# NRC7394-TX.net
KiCad netlist of a schematic drawn in Altium Designer
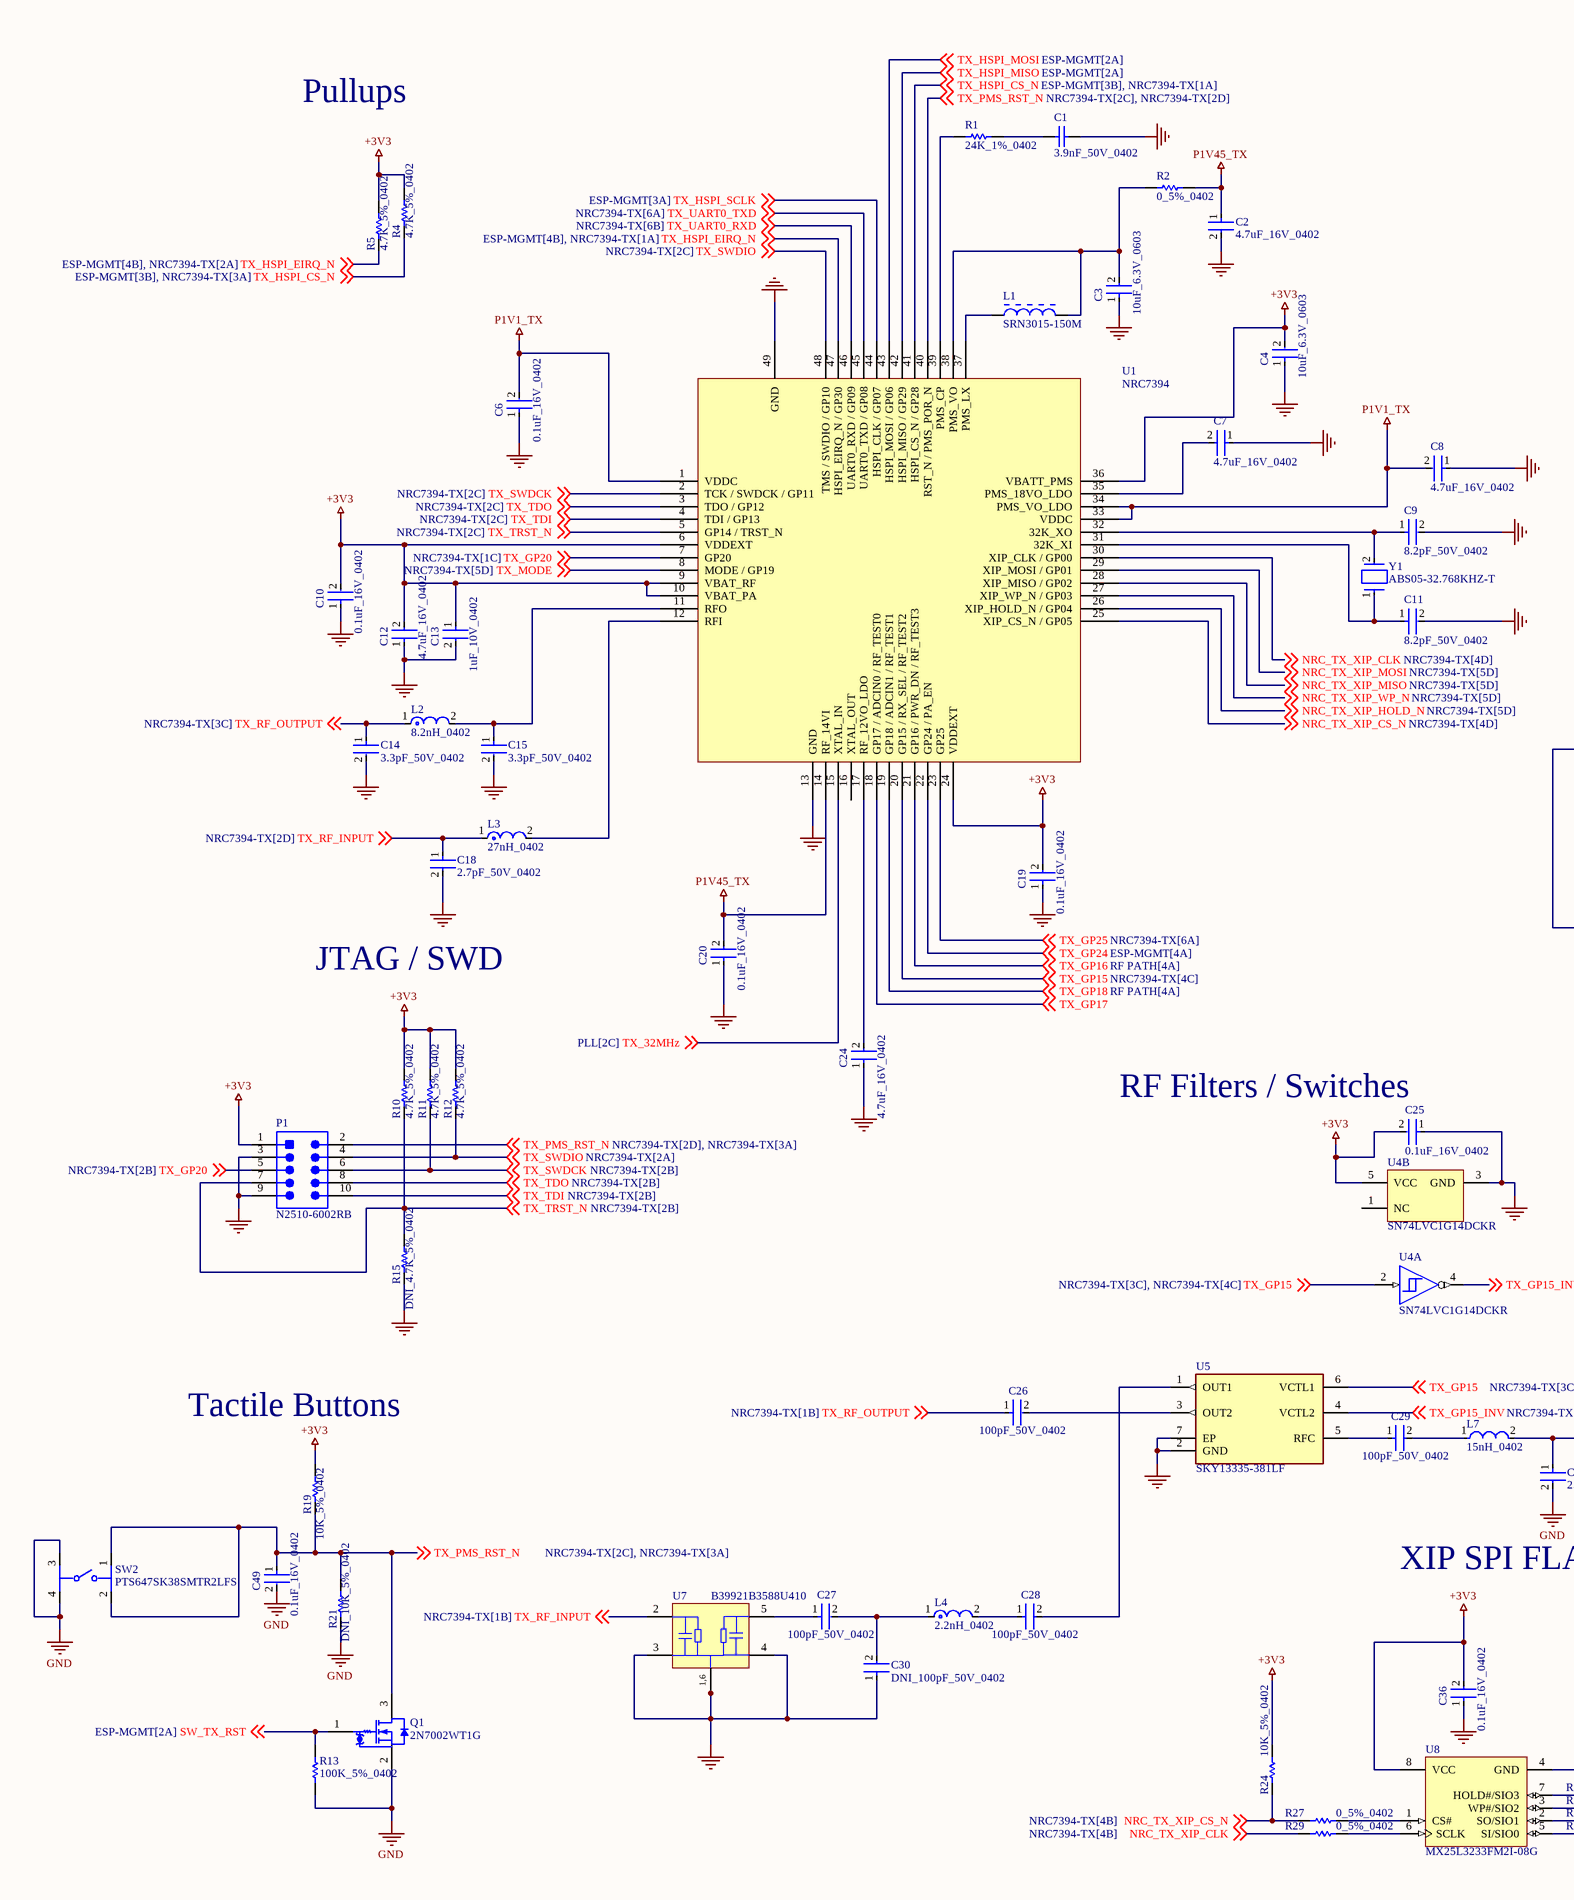
[diagram p0: NRC7394-TX.SchDoc, left]
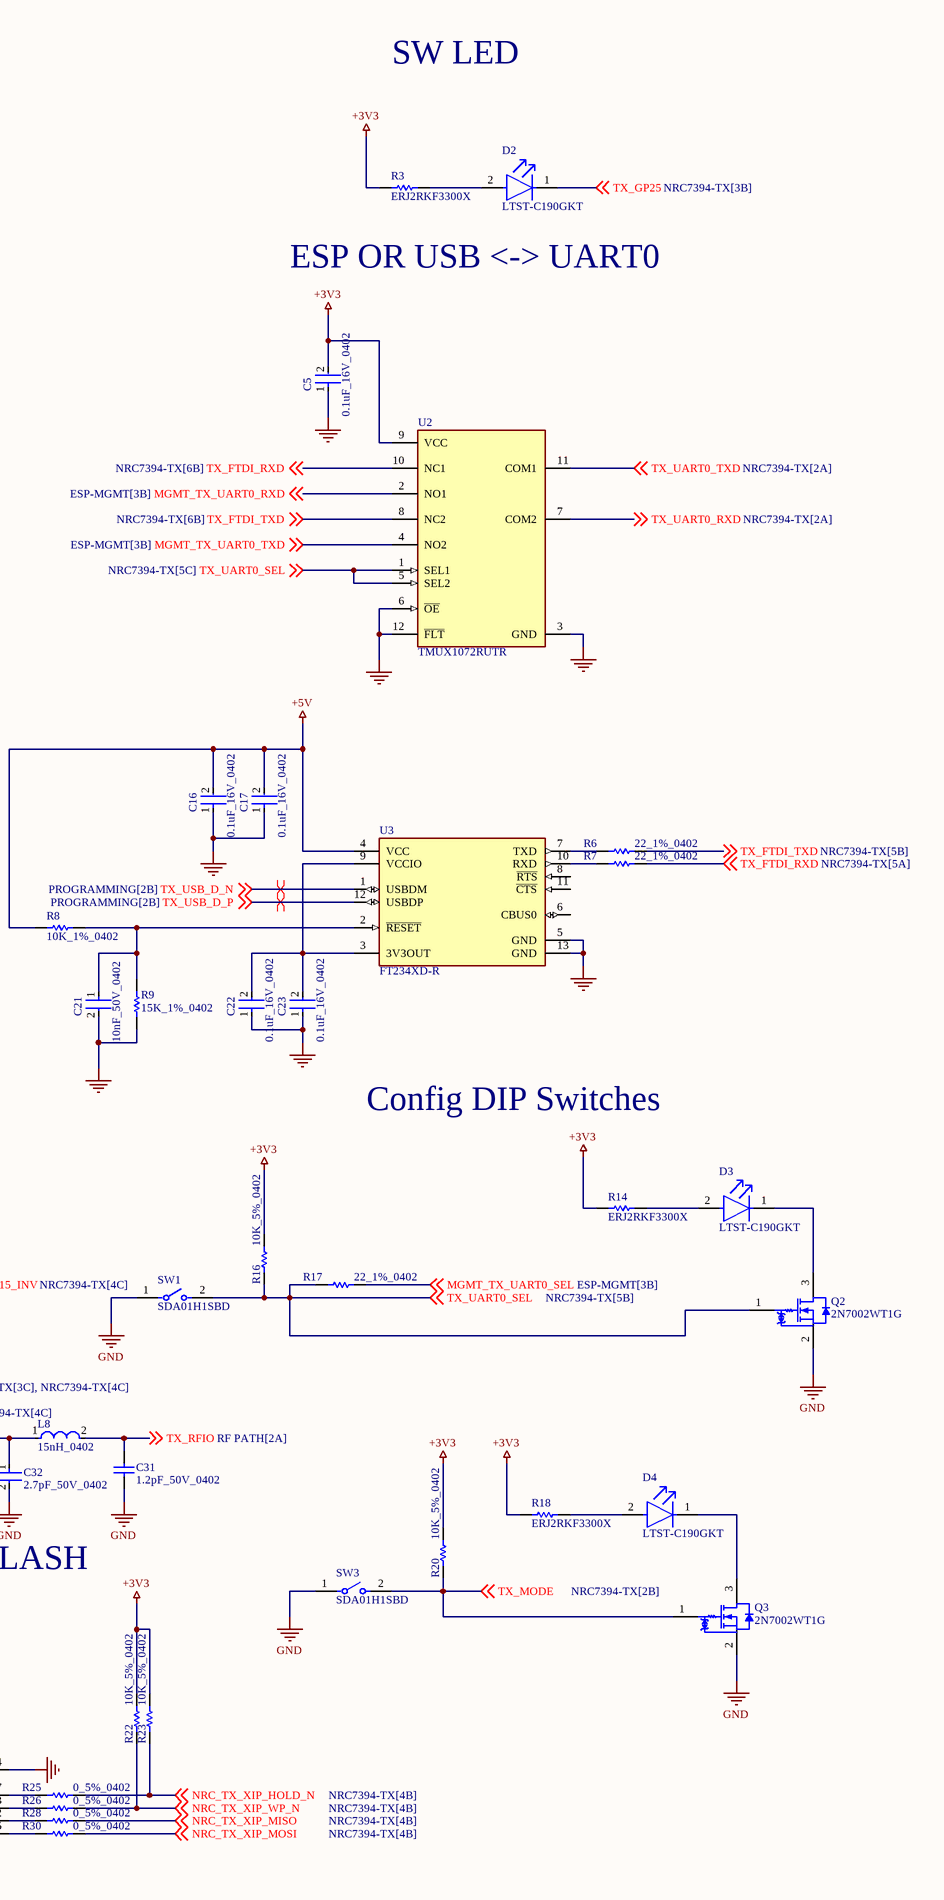
[diagram p1: NRC7394-TX.SchDoc, right]

(export (version "E")
  (design (tool "Eeschema 10.0.6"))
  (components
    (comp (ref "C1")
      (value "3.9nF_50V_0402")
      (footprint "CAPC1005X56X25LL10T15")
      (fields
        (field (name "MANUFACTURER") "AVX Interconnect / Elco")
        (field (name "PART NUMBER") "04025C392JAT2A")
      )
      (libsource (lib "Altium Content Vault") (part "CAP"))
    )
    (comp (ref "C2")
      (value "4.7uF_16V_0402")
      (footprint "FP-CL829-IPC_C")
      (description "Cap Ceramic 4.7uF 16V X5R ±20% SMD 0402 +85°C Paper T/R")
      (fields (field (name "TOLERANCE") "20%"))
      (libsource (lib "Altium Content Vault") (part "b4654b650e69147ec39a6b967a45e02"))
    )
    (comp (ref "C3")
      (value "10uF_6.3V_0603")
      (footprint "FP-GRM188-0_1-e0_2_0_55-IPC_A")
      (description "Chip Multilayer Ceramic Capacitors for General Purpose, 0603, 10uF, X5R, 15%, 20%, 6.3V")
      (fields (field (name "VOLTAGE") "6.3V") (field (name "TOLERANCE") "20%"))
      (libsource (lib "Altium Content Vault") (part "02cd4be3c70576c341d710602a673aa"))
    )
    (comp (ref "C4")
      (value "10uF_6.3V_0603")
      (footprint "FP-GRM188-0_1-e0_2_0_55-IPC_A")
      (description "Chip Multilayer Ceramic Capacitors for General Purpose, 0603, 10uF, X5R, 15%, 20%, 6.3V")
      (fields (field (name "VOLTAGE") "6.3V") (field (name "TOLERANCE") "20%"))
      (libsource (lib "Altium Content Vault") (part "02cd4be3c70576c341d710602a673aa"))
    )
    (comp (ref "C5")
      (value "0.1uF_16V_0402")
      (footprint "FP-C0402-BB-MFG")
      (description "CAP CER 0.1UF 16V 20% X7R 0402")
      (fields
        (field (name "MANUFACTURER") "Kemet")
        (field (name "OCTOPART") "https://octopart.com/c0402c104m4ractu-kemet-10476575")
      )
      (libsource (lib "Altium Content Vault") (part "b4654b650e69147ec39a6b967a45e02"))
    )
    (comp (ref "C6")
      (value "0.1uF_16V_0402")
      (footprint "FP-C0402-BB-MFG")
      (description "CAP CER 0.1UF 16V 20% X7R 0402")
      (fields
        (field (name "MANUFACTURER") "Kemet")
        (field (name "OCTOPART") "https://octopart.com/c0402c104m4ractu-kemet-10476575")
      )
      (libsource (lib "Altium Content Vault") (part "b4654b650e69147ec39a6b967a45e02"))
    )
    (comp (ref "C7")
      (value "4.7uF_16V_0402")
      (footprint "FP-CL829-IPC_C")
      (description "Cap Ceramic 4.7uF 16V X5R ±20% SMD 0402 +85°C Paper T/R")
      (fields (field (name "TOLERANCE") "20%"))
      (libsource (lib "Altium Content Vault") (part "b4654b650e69147ec39a6b967a45e02"))
    )
    (comp (ref "C8")
      (value "4.7uF_16V_0402")
      (footprint "FP-CL829-IPC_C")
      (description "Cap Ceramic 4.7uF 16V X5R ±20% SMD 0402 +85°C Paper T/R")
      (fields (field (name "TOLERANCE") "20%"))
      (libsource (lib "Altium Content Vault") (part "b4654b650e69147ec39a6b967a45e02"))
    )
    (comp (ref "C9")
      (value "8.2pF_50V_0402")
      (footprint "FP-C0402-BB-MFG")
      (description "CAP CER 8.2PF 50V NP0 0402")
      (fields
        (field (name "MANUFACTURER PART NUMBER") "C0402C829C5GACTU")
        (field (name "TOLERANCE") "0.25 pF")
      )
      (libsource (lib "Altium Content Vault") (part "b4654b650e69147ec39a6b967a45e02"))
    )
    (comp (ref "C10")
      (value "0.1uF_16V_0402")
      (footprint "FP-C0402-BB-MFG")
      (description "CAP CER 0.1UF 16V 20% X7R 0402")
      (fields
        (field (name "MANUFACTURER") "Kemet")
        (field (name "OCTOPART") "https://octopart.com/c0402c104m4ractu-kemet-10476575")
      )
      (libsource (lib "Altium Content Vault") (part "b4654b650e69147ec39a6b967a45e02"))
    )
    (comp (ref "C11")
      (value "8.2pF_50V_0402")
      (footprint "FP-C0402-BB-MFG")
      (description "CAP CER 8.2PF 50V NP0 0402")
      (fields
        (field (name "MANUFACTURER PART NUMBER") "C0402C829C5GACTU")
        (field (name "TOLERANCE") "0.25 pF")
      )
      (libsource (lib "Altium Content Vault") (part "b4654b650e69147ec39a6b967a45e02"))
    )
    (comp (ref "C12")
      (value "4.7uF_16V_0402")
      (footprint "FP-CL829-IPC_C")
      (description "Cap Ceramic 4.7uF 16V X5R ±20% SMD 0402 +85°C Paper T/R")
      (fields (field (name "TOLERANCE") "20%"))
      (libsource (lib "Altium Content Vault") (part "b4654b650e69147ec39a6b967a45e02"))
    )
    (comp (ref "C13")
      (value "1uF_10V_0402")
      (footprint "FP-C0402C105K8PACTU-MFG")
      (description "CAP CER 1UF 10V X5R 0402")
      (fields (field (name "VOLTAGE") "10V") (field (name "TOLERANCE") "10%"))
      (libsource (lib "Altium Content Vault") (part "11868f565c42a9108669ba33697ecf6"))
    )
    (comp (ref "C14")
      (value "3.3pF_50V_0402")
      (footprint "FP-C0402-BB-MFG")
      (description "Capacitor: ceramic; MLCC; 3.3pF; 50VDC; C0G; ±0.25pF; SMD; 0402")
      (fields
        (field (name "MANUFACTURER PART NUMBER") "C0402C339C5GACTU")
        (field (name "TOLERANCE") "0.25 pF")
      )
      (libsource (lib "Altium Content Vault") (part "b4654b650e69147ec39a6b967a45e02"))
    )
    (comp (ref "C15")
      (value "3.3pF_50V_0402")
      (footprint "FP-C0402-BB-MFG")
      (description "Capacitor: ceramic; MLCC; 3.3pF; 50VDC; C0G; ±0.25pF; SMD; 0402")
      (fields
        (field (name "MANUFACTURER PART NUMBER") "C0402C339C5GACTU")
        (field (name "TOLERANCE") "0.25 pF")
      )
      (libsource (lib "Altium Content Vault") (part "b4654b650e69147ec39a6b967a45e02"))
    )
    (comp (ref "C16")
      (value "0.1uF_16V_0402")
      (footprint "FP-C0402-BB-MFG")
      (description "CAP CER 0.1UF 16V 20% X7R 0402")
      (fields
        (field (name "MANUFACTURER") "Kemet")
        (field (name "OCTOPART") "https://octopart.com/c0402c104m4ractu-kemet-10476575")
      )
      (libsource (lib "Altium Content Vault") (part "b4654b650e69147ec39a6b967a45e02"))
    )
    (comp (ref "C17")
      (value "0.1uF_16V_0402")
      (footprint "FP-C0402-BB-MFG")
      (description "CAP CER 0.1UF 16V 20% X7R 0402")
      (fields
        (field (name "MANUFACTURER") "Kemet")
        (field (name "OCTOPART") "https://octopart.com/c0402c104m4ractu-kemet-10476575")
      )
      (libsource (lib "Altium Content Vault") (part "b4654b650e69147ec39a6b967a45e02"))
    )
    (comp (ref "C18")
      (value "2.7pF_50V_0402")
      (footprint "FP-GJM155-0_05-IPC_A")
      (description "Multi-Layer Ceramic Capacitor 2.7pF C0G  ±0.1pF 0402 Paper T/R")
      (fields (field (name "VOLTAGE") "50V"))
      (libsource (lib "Altium Content Vault") (part "02cd4be3c70576c341d710602a673aa"))
    )
    (comp (ref "C19")
      (value "0.1uF_16V_0402")
      (footprint "FP-C0402-BB-MFG")
      (description "CAP CER 0.1UF 16V 20% X7R 0402")
      (fields
        (field (name "MANUFACTURER") "Kemet")
        (field (name "OCTOPART") "https://octopart.com/c0402c104m4ractu-kemet-10476575")
      )
      (libsource (lib "Altium Content Vault") (part "b4654b650e69147ec39a6b967a45e02"))
    )
    (comp (ref "C20")
      (value "0.1uF_16V_0402")
      (footprint "FP-C0402-BB-MFG")
      (description "CAP CER 0.1UF 16V 20% X7R 0402")
      (fields
        (field (name "MANUFACTURER") "Kemet")
        (field (name "OCTOPART") "https://octopart.com/c0402c104m4ractu-kemet-10476575")
      )
      (libsource (lib "Altium Content Vault") (part "b4654b650e69147ec39a6b967a45e02"))
    )
    (comp (ref "C21")
      (value "10nF_50V_0402")
      (footprint "FP-CL165-IPC_C")
      (description "Cap Ceramic 10nF 50V X7R ±10% SMD 0402 +125°C Paper T/R")
      (fields (field (name "VOLTAGE") "50V") (field (name "TOLERANCE") "10%"))
      (libsource (lib "Altium Content Vault") (part "b4654b650e69147ec39a6b967a45e02"))
    )
    (comp (ref "C22")
      (value "0.1uF_16V_0402")
      (footprint "FP-C0402-BB-MFG")
      (description "CAP CER 0.1UF 16V 20% X7R 0402")
      (fields
        (field (name "MANUFACTURER") "Kemet")
        (field (name "OCTOPART") "https://octopart.com/c0402c104m4ractu-kemet-10476575")
      )
      (libsource (lib "Altium Content Vault") (part "b4654b650e69147ec39a6b967a45e02"))
    )
    (comp (ref "C23")
      (value "0.1uF_16V_0402")
      (footprint "FP-C0402-BB-MFG")
      (description "CAP CER 0.1UF 16V 20% X7R 0402")
      (fields
        (field (name "MANUFACTURER") "Kemet")
        (field (name "OCTOPART") "https://octopart.com/c0402c104m4ractu-kemet-10476575")
      )
      (libsource (lib "Altium Content Vault") (part "b4654b650e69147ec39a6b967a45e02"))
    )
    (comp (ref "C24")
      (value "4.7uF_16V_0402")
      (footprint "FP-CL829-IPC_C")
      (description "Cap Ceramic 4.7uF 16V X5R ±20% SMD 0402 +85°C Paper T/R")
      (fields (field (name "TOLERANCE") "20%"))
      (libsource (lib "Altium Content Vault") (part "b4654b650e69147ec39a6b967a45e02"))
    )
    (comp (ref "C25")
      (value "0.1uF_16V_0402")
      (footprint "FP-C0402-BB-MFG")
      (description "CAP CER 0.1UF 16V 20% X7R 0402")
      (fields
        (field (name "MANUFACTURER") "Kemet")
        (field (name "OCTOPART") "https://octopart.com/c0402c104m4ractu-kemet-10476575")
      )
      (libsource (lib "Altium Content Vault") (part "b4654b650e69147ec39a6b967a45e02"))
    )
    (comp (ref "C26")
      (value "100pF_50V_0402")
      (footprint "FP-C0402-BB-MFG")
      (description "CAP CER 100PF 50V C0G/NP0 0402")
      (fields (field (name "MANUFACTURER") "Kemet") (field (name "TOLERANCE") "0.05"))
      (libsource (lib "Altium Content Vault") (part "b4654b650e69147ec39a6b967a45e02"))
    )
    (comp (ref "C27")
      (value "100pF_50V_0402")
      (footprint "FP-C0402-BB-MFG")
      (description "CAP CER 100PF 50V C0G/NP0 0402")
      (fields (field (name "MANUFACTURER") "Kemet") (field (name "TOLERANCE") "0.05"))
      (libsource (lib "Altium Content Vault") (part "b4654b650e69147ec39a6b967a45e02"))
    )
    (comp (ref "C28")
      (value "100pF_50V_0402")
      (footprint "FP-C0402-BB-MFG")
      (description "CAP CER 100PF 50V C0G/NP0 0402")
      (fields (field (name "MANUFACTURER") "Kemet") (field (name "TOLERANCE") "0.05"))
      (libsource (lib "Altium Content Vault") (part "b4654b650e69147ec39a6b967a45e02"))
    )
    (comp (ref "C29")
      (value "100pF_50V_0402")
      (footprint "FP-C0402-BB-MFG")
      (description "CAP CER 100PF 50V C0G/NP0 0402")
      (fields (field (name "MANUFACTURER") "Kemet") (field (name "TOLERANCE") "0.05"))
      (libsource (lib "Altium Content Vault") (part "b4654b650e69147ec39a6b967a45e02"))
    )
    (comp (ref "C30")
      (value "DNI_100pF_50V_0402")
      (footprint "FP-C0402-BB-MFG")
      (description "CAP CER 100PF 50V C0G/NP0 0402")
      (fields (field (name "MANUFACTURER") "Kemet") (field (name "TOLERANCE") "0.05"))
      (libsource (lib "Altium Content Vault") (part "b4654b650e69147ec39a6b967a45e02"))
    )
    (comp (ref "C31")
      (value "1.2pF_50V_0402")
      (footprint "CAPC1006X50X20LL10T10")
      (fields
        (field (name "MANUFACTURER") "AVX Interconnect / Elco")
        (field (name "PART NUMBER") "04023J1R2BBSTR")
      )
      (libsource (lib "Altium Content Vault") (part "CAP"))
    )
    (comp (ref "C32")
      (value "2.7pF_50V_0402")
      (footprint "FP-GJM155-0_05-IPC_A")
      (description "Multi-Layer Ceramic Capacitor 2.7pF C0G  ±0.1pF 0402 Paper T/R")
      (fields (field (name "VOLTAGE") "50V"))
      (libsource (lib "Altium Content Vault") (part "02cd4be3c70576c341d710602a673aa"))
    )
    (comp (ref "C36")
      (value "0.1uF_16V_0402")
      (footprint "FP-C0402-BB-MFG")
      (description "CAP CER 0.1UF 16V 20% X7R 0402")
      (fields
        (field (name "MANUFACTURER") "Kemet")
        (field (name "OCTOPART") "https://octopart.com/c0402c104m4ractu-kemet-10476575")
      )
      (libsource (lib "Altium Content Vault") (part "b4654b650e69147ec39a6b967a45e02"))
    )
    (comp (ref "C49")
      (value "0.1uF_16V_0402")
      (footprint "FP-C0402-BB-MFG")
      (description "CAP CER 0.1UF 16V 20% X7R 0402")
      (fields
        (field (name "MANUFACTURER") "Kemet")
        (field (name "OCTOPART") "https://octopart.com/c0402c104m4ractu-kemet-10476575")
      )
      (libsource (lib "Altium Content Vault") (part "b4654b650e69147ec39a6b967a45e02"))
    )
    (comp (ref "D2")
      (value "LTST-C190GKT")
      (footprint "FP-LTST-C190GKT-MFG")
      (description "LED GREEN CLEAR CHIP SMD")
      (fields (field (name "VOLTAGE") "2V"))
      (libsource (lib "Altium Content Vault") (part "8706943c75ba83719d021d2fdc84c58"))
    )
    (comp (ref "D3")
      (value "LTST-C190GKT")
      (footprint "FP-LTST-C190GKT-MFG")
      (description "LED GREEN CLEAR CHIP SMD")
      (fields (field (name "VOLTAGE") "2V"))
      (libsource (lib "Altium Content Vault") (part "8706943c75ba83719d021d2fdc84c58"))
    )
    (comp (ref "D4")
      (value "LTST-C190GKT")
      (footprint "FP-LTST-C190GKT-MFG")
      (description "LED GREEN CLEAR CHIP SMD")
      (fields (field (name "VOLTAGE") "2V"))
      (libsource (lib "Altium Content Vault") (part "8706943c75ba83719d021d2fdc84c58"))
    )
    (comp (ref "L1")
      (value "SRN3015-150M")
      (footprint "BOUR-SRN3015-2_V")
      (fields (field (name "MANUFACTURER") "Bourns"))
      (libsource (lib "Altium Content Vault") (part "BOUR-IND-2A"))
    )
    (comp (ref "L2")
      (value "8.2nH_0402")
      (footprint "FP-LQG15HH_02-IPC_B")
      (description "Multilayer type RF Inductor 8.2nH ±5% 0.24Ω 550mA 0402")
      (fields (field (name "TOLERANCE") "5%"))
      (libsource (lib "Altium Content Vault") (part "4cc4b267dca4c8e51f7102f422741d8"))
    )
    (comp (ref "L3")
      (value "27nH_0402")
      (footprint "FP-LQG15HH_02-IPC_C")
      (description "Multilayer type RF Inductor 27nH ±5% 0.46Ω 350mA 0402")
      (fields (field (name "TOLERANCE") "5%"))
      (libsource (lib "Altium Content Vault") (part "4cc4b267dca4c8e51f7102f422741d8"))
    )
    (comp (ref "L4")
      (value "2.2nH_0402")
      (footprint "FP-LQG15HH_02-IPC_C")
      (description "Multilayer type RF Inductor 2.2nH ±0.3nH 0.09Ω 900mA 0402")
      (libsource (lib "Altium Content Vault") (part "4cc4b267dca4c8e51f7102f422741d8"))
    )
    (comp (ref "L7")
      (value "15nH_0402")
      (footprint "FP-HK1005-MFG")
      (description "FIXED IND 15NH 320MA 460 MOHM")
      (fields (field (name "TOLERANCE") "5%"))
      (libsource (lib "Altium Content Vault") (part "725321dda6339637d4d059423bc1c3c"))
    )
    (comp (ref "L8")
      (value "15nH_0402")
      (footprint "FP-HK1005-MFG")
      (description "FIXED IND 15NH 320MA 460 MOHM")
      (fields (field (name "TOLERANCE") "5%"))
      (libsource (lib "Altium Content Vault") (part "725321dda6339637d4d059423bc1c3c"))
    )
    (comp (ref "P1")
      (value "N2510-6002RB")
      (footprint "3M-N2510-6002-10_V")
      (fields (field (name "PARTNUMBER") "N2510") (field (name "MANUFACTURER") "3M"))
      (libsource (lib "Altium Content Vault") (part "CN-2P-M-R10"))
    )
    (comp (ref "Q1")
      (value "2N7002WT1G")
      (footprint "ONSC-SC-70-3-419-04_V")
      (description "Small Signal MOSFET, 60 V, 340 mA, Single, N-Channel, 3-Pin SC70, Pb-Free, Tape and Reel")
      (fields (field (name "MANUFACTURER") "On Semiconductor"))
      (libsource (lib "Altium Content Vault") (part "ONSC-NMOS-G1S2D3-3_C"))
    )
    (comp (ref "Q2")
      (value "2N7002WT1G")
      (footprint "ONSC-SC-70-3-419-04_V")
      (description "Small Signal MOSFET, 60 V, 340 mA, Single, N-Channel, 3-Pin SC70, Pb-Free, Tape and Reel")
      (fields (field (name "MANUFACTURER") "On Semiconductor"))
      (libsource (lib "Altium Content Vault") (part "ONSC-NMOS-G1S2D3-3_C"))
    )
    (comp (ref "Q3")
      (value "2N7002WT1G")
      (footprint "ONSC-SC-70-3-419-04_V")
      (description "Small Signal MOSFET, 60 V, 340 mA, Single, N-Channel, 3-Pin SC70, Pb-Free, Tape and Reel")
      (fields (field (name "MANUFACTURER") "On Semiconductor"))
      (libsource (lib "Altium Content Vault") (part "ONSC-NMOS-G1S2D3-3_C"))
    )
    (comp (ref "R1")
      (value "24K_1%_0402")
      (footprint "RESC1005X40X25ML05T05")
      (fields (field (name "PART NUMBER") "CRCW040224K0FKED") (field (name "MANUFACTURER") "Vishay Dale"))
      (libsource (lib "Altium Content Vault") (part "RES"))
    )
    (comp (ref "R2")
      (value "0_5%_0402")
      (footprint "RESC1005X40X25ML05T10")
      (fields (field (name "MANUFACTURER") "Panasonic") (field (name "PART NUMBER") "ERJ-U020R00X"))
      (libsource (lib "Altium Content Vault") (part "RES"))
    )
    (comp (ref "R3")
      (value "ERJ2RKF3300X")
      (footprint "RESC1005X40X25ML05T05")
      (fields (field (name "MANUFACTURER") "Panasonic"))
      (libsource (lib "Altium Content Vault") (part "RES"))
    )
    (comp (ref "R4")
      (value "4.7K_5%_0402")
      (footprint "RESC1005X40X25LL05T05")
      (fields (field (name "PART NUMBER") "CRCW04024K70JNTD") (field (name "MANUFACTURER") "Vishay Dale"))
      (libsource (lib "Altium Content Vault") (part "RES"))
    )
    (comp (ref "R5")
      (value "4.7K_5%_0402")
      (footprint "RESC1005X40X25LL05T05")
      (fields (field (name "PART NUMBER") "CRCW04024K70JNTD") (field (name "MANUFACTURER") "Vishay Dale"))
      (libsource (lib "Altium Content Vault") (part "RES"))
    )
    (comp (ref "R6")
      (value "22_1%_0402")
      (footprint "RESC1005X40X25LL05T10")
      (fields (field (name "MANUFACTURER") "Yageo / Phycomp") (field (name "PART NUMBER") "RC0402FR-0722RL"))
      (libsource (lib "Altium Content Vault") (part "RES"))
    )
    (comp (ref "R7")
      (value "22_1%_0402")
      (footprint "RESC1005X40X25LL05T10")
      (fields (field (name "MANUFACTURER") "Yageo / Phycomp") (field (name "PART NUMBER") "RC0402FR-0722RL"))
      (libsource (lib "Altium Content Vault") (part "RES"))
    )
    (comp (ref "R8")
      (value "10K_1%_0402")
      (footprint "RESC1005X40X25NL05T10")
      (fields (field (name "MANUFACTURER") "Multicomp") (field (name "PART NUMBER") "MCMR04X103 JTL"))
      (libsource (lib "Altium Content Vault") (part "RES"))
    )
    (comp (ref "R9")
      (value "15K_1%_0402")
      (footprint "RESC1005X40X25ML05T10")
      (fields (field (name "MANUFACTURER") "Yageo") (field (name "PART NUMBER") "RC0402JR-1315KL"))
      (libsource (lib "Altium Content Vault") (part "RES"))
    )
    (comp (ref "R10")
      (value "4.7K_5%_0402")
      (footprint "RESC1005X40X25LL05T05")
      (fields (field (name "PART NUMBER") "CRCW04024K70JNTD") (field (name "MANUFACTURER") "Vishay Dale"))
      (libsource (lib "Altium Content Vault") (part "RES"))
    )
    (comp (ref "R11")
      (value "4.7K_5%_0402")
      (footprint "RESC1005X40X25LL05T05")
      (fields (field (name "PART NUMBER") "CRCW04024K70JNTD") (field (name "MANUFACTURER") "Vishay Dale"))
      (libsource (lib "Altium Content Vault") (part "RES"))
    )
    (comp (ref "R12")
      (value "4.7K_5%_0402")
      (footprint "RESC1005X40X25LL05T05")
      (fields (field (name "PART NUMBER") "CRCW04024K70JNTD") (field (name "MANUFACTURER") "Vishay Dale"))
      (libsource (lib "Altium Content Vault") (part "RES"))
    )
    (comp (ref "R13")
      (value "100K_5%_0402")
      (footprint "RESC1005X37X25ML05T10")
      (fields (field (name "PART NUMBER") "RE0402DR-07100KL") (field (name "MANUFACTURER") "Yageo / Phycomp"))
      (libsource (lib "Altium Content Vault") (part "RES"))
    )
    (comp (ref "R14")
      (value "ERJ2RKF3300X")
      (footprint "RESC1005X40X25ML05T05")
      (fields (field (name "MANUFACTURER") "Panasonic"))
      (libsource (lib "Altium Content Vault") (part "RES"))
    )
    (comp (ref "R15")
      (value "DNI_4.7K_5%_0402")
      (footprint "RESC1005X40X25LL05T05")
      (fields (field (name "PART NUMBER") "CRCW04024K70JNTD") (field (name "MANUFACTURER") "Vishay Dale"))
      (libsource (lib "Altium Content Vault") (part "RES"))
    )
    (comp (ref "R16")
      (value "10K_5%_0402")
      (footprint "RESC1005X40X25ML05T05")
      (fields (field (name "MANUFACTURER") "Panasonic") (field (name "PART NUMBER") "ERT-J0EM103J"))
      (libsource (lib "Altium Content Vault") (part "RES"))
    )
    (comp (ref "R17")
      (value "22_1%_0402")
      (footprint "RESC1005X40X25LL05T10")
      (fields (field (name "MANUFACTURER") "Yageo / Phycomp") (field (name "PART NUMBER") "RC0402FR-0722RL"))
      (libsource (lib "Altium Content Vault") (part "RES"))
    )
    (comp (ref "R18")
      (value "ERJ2RKF3300X")
      (footprint "RESC1005X40X25ML05T05")
      (fields (field (name "MANUFACTURER") "Panasonic"))
      (libsource (lib "Altium Content Vault") (part "RES"))
    )
    (comp (ref "R19")
      (value "10K_5%_0402")
      (footprint "RESC1005X40X25ML05T05")
      (fields (field (name "MANUFACTURER") "Panasonic") (field (name "PART NUMBER") "ERT-J0EM103J"))
      (libsource (lib "Altium Content Vault") (part "RES"))
    )
    (comp (ref "R20")
      (value "10K_5%_0402")
      (footprint "RESC1005X40X25ML05T05")
      (fields (field (name "MANUFACTURER") "Panasonic") (field (name "PART NUMBER") "ERT-J0EM103J"))
      (libsource (lib "Altium Content Vault") (part "RES"))
    )
    (comp (ref "R21")
      (value "DNI_10K_5%_0402")
      (footprint "RESC1005X40X25ML05T05")
      (fields (field (name "MANUFACTURER") "Panasonic") (field (name "PART NUMBER") "ERT-J0EM103J"))
      (libsource (lib "Altium Content Vault") (part "RES"))
    )
    (comp (ref "R22")
      (value "10K_5%_0402")
      (footprint "RESC1005X40X25ML05T05")
      (fields (field (name "MANUFACTURER") "Panasonic") (field (name "PART NUMBER") "ERT-J0EM103J"))
      (libsource (lib "Altium Content Vault") (part "RES"))
    )
    (comp (ref "R23")
      (value "10K_5%_0402")
      (footprint "RESC1005X40X25ML05T05")
      (fields (field (name "MANUFACTURER") "Panasonic") (field (name "PART NUMBER") "ERT-J0EM103J"))
      (libsource (lib "Altium Content Vault") (part "RES"))
    )
    (comp (ref "R24")
      (value "10K_5%_0402")
      (footprint "RESC1005X40X25ML05T05")
      (fields (field (name "MANUFACTURER") "Panasonic") (field (name "PART NUMBER") "ERT-J0EM103J"))
      (libsource (lib "Altium Content Vault") (part "RES"))
    )
    (comp (ref "R25")
      (value "0_5%_0402")
      (footprint "RESC1005X40X25ML05T10")
      (fields (field (name "MANUFACTURER") "Panasonic") (field (name "PART NUMBER") "ERJ-U020R00X"))
      (libsource (lib "Altium Content Vault") (part "RES"))
    )
    (comp (ref "R26")
      (value "0_5%_0402")
      (footprint "RESC1005X40X25ML05T10")
      (fields (field (name "MANUFACTURER") "Panasonic") (field (name "PART NUMBER") "ERJ-U020R00X"))
      (libsource (lib "Altium Content Vault") (part "RES"))
    )
    (comp (ref "R27")
      (value "0_5%_0402")
      (footprint "RESC1005X40X25ML05T10")
      (fields (field (name "MANUFACTURER") "Panasonic") (field (name "PART NUMBER") "ERJ-U020R00X"))
      (libsource (lib "Altium Content Vault") (part "RES"))
    )
    (comp (ref "R28")
      (value "0_5%_0402")
      (footprint "RESC1005X40X25ML05T10")
      (fields (field (name "MANUFACTURER") "Panasonic") (field (name "PART NUMBER") "ERJ-U020R00X"))
      (libsource (lib "Altium Content Vault") (part "RES"))
    )
    (comp (ref "R29")
      (value "0_5%_0402")
      (footprint "RESC1005X40X25ML05T10")
      (fields (field (name "MANUFACTURER") "Panasonic") (field (name "PART NUMBER") "ERJ-U020R00X"))
      (libsource (lib "Altium Content Vault") (part "RES"))
    )
    (comp (ref "R30")
      (value "0_5%_0402")
      (footprint "RESC1005X40X25ML05T10")
      (fields (field (name "MANUFACTURER") "Panasonic") (field (name "PART NUMBER") "ERJ-U020R00X"))
      (libsource (lib "Altium Content Vault") (part "RES"))
    )
    (comp (ref "SW1")
      (value "SDA01H1SBD")
      (footprint "FP-SDA01H1SBD-MFG")
      (description "SWITCH SLIDE DIP SPST 25MA 24V")
      (fields
        (field (name "OCTOPART") "https://octopart.com/sda01h1sbd-c%26k+components-7089741")
        (field (name "MANUFACTURER") "C&K Components")
      )
      (libsource (lib "Altium Content Vault") (part "bb27bde45df87f1f469753f287ef5ae"))
    )
    (comp (ref "SW2")
      (value "PTS647SK38SMTR2LFS")
      (footprint "FP-PTS647SK38SMTR2LFS-MFG")
      (description "TACT 4.5 X 4.5, 3.8 MM H, 2.5N,")
      (libsource (lib "Altium Content Vault") (part "1adf0dd01260c80cf25a44bfd6b99ba"))
    )
    (comp (ref "SW3")
      (value "SDA01H1SBD")
      (footprint "FP-SDA01H1SBD-MFG")
      (description "SWITCH SLIDE DIP SPST 25MA 24V")
      (fields
        (field (name "OCTOPART") "https://octopart.com/sda01h1sbd-c%26k+components-7089741")
        (field (name "MANUFACTURER") "C&K Components")
      )
      (libsource (lib "Altium Content Vault") (part "bb27bde45df87f1f469753f287ef5ae"))
    )
    (comp (ref "U1")
      (value "NRC7394")
      (footprint "QFN48_6X6")
      (description "NRC7394 WiFi HaLow chipset")
      (libsource (lib "NRC7394") (part "NRC7394"))
    )
    (comp (ref "U2")
      (value "TMUX1072RUTR")
      (footprint "FP-RUT0012A-MFG")
      (description "IC SWITCH SPDT DUAL 12UQFN")
      (libsource (lib "Altium Content Vault") (part "12a319ab100cd6cfe745e35972674f5"))
    )
    (comp (ref "U3")
      (value "FT234XD-R")
      (footprint "FP-DFN-12-IPC_B")
      (description "IC USB SERIAL BASIC UART 12DFN")
      (libsource (lib "Altium Content Vault") (part "4bef3367ed9f9051bcb84ab46edda1c"))
    )
    (comp (ref "U4")
      (value "SN74LVC1G14DCKR")
      (footprint "DCK0005A_L")
      (description "Single Schmitt-Trigger Inverter, DCK0005A, LARGE T&R")
      (fields
        (field (name "GENERIC PART NUMBER") "SN74LVC1G14")
        (field (name "MANUFACTURER") "Texas Instruments")
      )
      (libsource (lib "Altium Content Vault") (part "TI-SN74XXX1XX4-XX-5-SCHMITT"))
    )
    (comp (ref "U5")
      (value "SKY13335-381LF")
      (footprint "FP-SKY13335-381LF-MFG")
      (description "IC RF SWITCH SPDT 6GHZ 6MLPD")
      (libsource (lib "Altium Content Vault") (part "beb9d273cf817256a5bcdae75b1af25"))
    )
    (comp (ref "U7")
      (value "B39921B3588U410")
      (footprint "EPCO-DCC6C-6")
      (description "SAW RF Filter, 915 MHz, -45 to 125 degC, 6-Pin SMD, RoHS, Tape and Reel")
      (fields (field (name "MANUFACTURER") "EPCOS"))
      (libsource (lib "Altium Content Vault") (part "EPCO-B3588-6"))
    )
    (comp (ref "U8")
      (value "MX25L3233FM2I-08G")
      (footprint "MXIC-SOP-8_M")
      (fields (field (name "MANUFACTURER") "Macronix"))
      (libsource (lib "Altium Content Vault") (part "MXIC-MX25L3233FM2I-08G-SOP-8"))
    )
    (comp (ref "Y1")
      (value "ABS05-32.768KHZ-T")
      (footprint "FP-ABS05-MFG")
      (description "Crystal 32.768kHz ±20ppm (Tol) 12.5pF FUND 90kΩ 2-Pin SMD T/R")
      (fields (field (name "TOLERANCE") "20ppm"))
      (libsource (lib "Altium Content Vault") (part "c23a69dc6c9e2f18f2079038eb95dd1"))
    )
  )
  (nets
    (net (code "1") (name "+3V3") (class "Default")
      (node (ref "C10") (pin "2") (pinfunction "2_2") (pintype "passive"))
      (node (ref "C12") (pin "2") (pinfunction "2_2") (pintype "passive"))
      (node (ref "C13") (pin "1") (pinfunction "1_1") (pintype "passive"))
      (node (ref "C19") (pin "2") (pinfunction "2_2") (pintype "passive"))
      (node (ref "C25") (pin "2") (pinfunction "2_2") (pintype "passive"))
      (node (ref "C36") (pin "2") (pinfunction "2_2") (pintype "passive"))
      (node (ref "C4") (pin "2") (pinfunction "2_2") (pintype "passive"))
      (node (ref "C5") (pin "2") (pinfunction "2_2") (pintype "passive"))
      (node (ref "P1") (pin "1") (pinfunction "1_1") (pintype "passive"))
      (node (ref "R10") (pin "2") (pinfunction "2_2") (pintype "passive"))
      (node (ref "R11") (pin "2") (pinfunction "2_2") (pintype "passive"))
      (node (ref "R12") (pin "2") (pinfunction "2_2") (pintype "passive"))
      (node (ref "R14") (pin "1") (pinfunction "1_1") (pintype "passive"))
      (node (ref "R16") (pin "2") (pinfunction "2_2") (pintype "passive"))
      (node (ref "R18") (pin "1") (pinfunction "1_1") (pintype "passive"))
      (node (ref "R19") (pin "2") (pinfunction "2_2") (pintype "passive"))
      (node (ref "R20") (pin "2") (pinfunction "2_2") (pintype "passive"))
      (node (ref "R22") (pin "2") (pinfunction "2_2") (pintype "passive"))
      (node (ref "R23") (pin "2") (pinfunction "2_2") (pintype "passive"))
      (node (ref "R24") (pin "2") (pinfunction "2_2") (pintype "passive"))
      (node (ref "R3") (pin "1") (pinfunction "1_1") (pintype "passive"))
      (node (ref "R4") (pin "2") (pinfunction "2_2") (pintype "passive"))
      (node (ref "R5") (pin "2") (pinfunction "2_2") (pintype "passive"))
      (node (ref "U1") (pin "10") (pinfunction "VBAT_PA_10") (pintype "passive"))
      (node (ref "U1") (pin "24") (pinfunction "VDDEXT_24") (pintype "passive"))
      (node (ref "U1") (pin "36") (pinfunction "VBATT_PMS_36") (pintype "passive"))
      (node (ref "U1") (pin "6") (pinfunction "VDDEXT_6") (pintype "passive"))
      (node (ref "U1") (pin "9") (pinfunction "VBAT_RF_9") (pintype "passive"))
      (node (ref "U2") (pin "9") (pinfunction "VCC_9") (pintype "power_in"))
      (node (ref "U4") (pin "5") (pinfunction "VCC_5") (pintype "power_in"))
      (node (ref "U8") (pin "8") (pinfunction "VCC_8") (pintype "power_in"))
    )
    (net (code "2") (name "+5V") (class "Default")
      (node (ref "C16") (pin "2") (pinfunction "2_2") (pintype "passive"))
      (node (ref "C17") (pin "2") (pinfunction "2_2") (pintype "passive"))
      (node (ref "R8") (pin "1") (pinfunction "1_1") (pintype "passive"))
      (node (ref "U3") (pin "4") (pinfunction "VCC_4") (pintype "power_in"))
    )
    (net (code "3") (name "GND") (class "Default")
      (node (ref "C1") (pin "2") (pinfunction "2_2") (pintype "passive"))
      (node (ref "C10") (pin "1") (pinfunction "1_1") (pintype "passive"))
      (node (ref "C11") (pin "2") (pinfunction "2_2") (pintype "passive"))
      (node (ref "C12") (pin "1") (pinfunction "1_1") (pintype "passive"))
      (node (ref "C13") (pin "2") (pinfunction "2_2") (pintype "passive"))
      (node (ref "C14") (pin "2") (pinfunction "2_2") (pintype "passive"))
      (node (ref "C15") (pin "2") (pinfunction "2_2") (pintype "passive"))
      (node (ref "C16") (pin "1") (pinfunction "1_1") (pintype "passive"))
      (node (ref "C17") (pin "1") (pinfunction "1_1") (pintype "passive"))
      (node (ref "C18") (pin "2") (pinfunction "2_2") (pintype "passive"))
      (node (ref "C19") (pin "1") (pinfunction "1_1") (pintype "passive"))
      (node (ref "C2") (pin "2") (pinfunction "2_2") (pintype "passive"))
      (node (ref "C20") (pin "1") (pinfunction "1_1") (pintype "passive"))
      (node (ref "C21") (pin "2") (pinfunction "2_2") (pintype "passive"))
      (node (ref "C22") (pin "1") (pinfunction "1_1") (pintype "passive"))
      (node (ref "C23") (pin "1") (pinfunction "1_1") (pintype "passive"))
      (node (ref "C24") (pin "1") (pinfunction "1_1") (pintype "passive"))
      (node (ref "C25") (pin "1") (pinfunction "1_1") (pintype "passive"))
      (node (ref "C3") (pin "1") (pinfunction "1_1") (pintype "passive"))
      (node (ref "C30") (pin "1") (pinfunction "1_1") (pintype "passive"))
      (node (ref "C31") (pin "1") (pinfunction "1_1") (pintype "passive"))
      (node (ref "C32") (pin "2") (pinfunction "2_2") (pintype "passive"))
      (node (ref "C36") (pin "1") (pinfunction "1_1") (pintype "passive"))
      (node (ref "C4") (pin "1") (pinfunction "1_1") (pintype "passive"))
      (node (ref "C49") (pin "2") (pinfunction "2_2") (pintype "passive"))
      (node (ref "C5") (pin "1") (pinfunction "1_1") (pintype "passive"))
      (node (ref "C6") (pin "1") (pinfunction "1_1") (pintype "passive"))
      (node (ref "C7") (pin "1") (pinfunction "1_1") (pintype "passive"))
      (node (ref "C8") (pin "1") (pinfunction "1_1") (pintype "passive"))
      (node (ref "C9") (pin "2") (pinfunction "2_2") (pintype "passive"))
      (node (ref "P1") (pin "3") (pinfunction "3_3") (pintype "passive"))
      (node (ref "P1") (pin "9") (pinfunction "9_9") (pintype "passive"))
      (node (ref "Q1") (pin "2") (pinfunction "S_2") (pintype "passive"))
      (node (ref "Q2") (pin "2") (pinfunction "S_2") (pintype "passive"))
      (node (ref "Q3") (pin "2") (pinfunction "S_2") (pintype "passive"))
      (node (ref "R13") (pin "1") (pinfunction "1_1") (pintype "passive"))
      (node (ref "R15") (pin "1") (pinfunction "1_1") (pintype "passive"))
      (node (ref "R21") (pin "1") (pinfunction "1_1") (pintype "passive"))
      (node (ref "R9") (pin "1") (pinfunction "1_1") (pintype "passive"))
      (node (ref "SW1") (pin "1") (pinfunction "1_1") (pintype "passive"))
      (node (ref "SW2") (pin "3") (pinfunction "3_3") (pintype "passive"))
      (node (ref "SW2") (pin "4") (pinfunction "4_4") (pintype "passive"))
      (node (ref "SW3") (pin "1") (pinfunction "1_1") (pintype "passive"))
      (node (ref "U1") (pin "13") (pinfunction "GND_13") (pintype "passive"))
      (node (ref "U1") (pin "49") (pinfunction "GND_49") (pintype "passive"))
      (node (ref "U2") (pin "12") (pinfunction "~{FLT}_12") (pintype "open_collector"))
      (node (ref "U2") (pin "3") (pinfunction "GND_3") (pintype "power_in"))
      (node (ref "U2") (pin "6") (pinfunction "~{OE}_6") (pintype "input"))
      (node (ref "U3") (pin "13") (pinfunction "GND_13") (pintype "power_in"))
      (node (ref "U3") (pin "5") (pinfunction "GND_5") (pintype "power_in"))
      (node (ref "U4") (pin "3") (pinfunction "GND_3") (pintype "power_in"))
      (node (ref "U5") (pin "2") (pinfunction "GND_2") (pintype "power_in"))
      (node (ref "U5") (pin "7") (pinfunction "EP_7") (pintype "power_in"))
      (node (ref "U7") (pin "1") (pinfunction "GND_1") (pintype "passive"))
      (node (ref "U7") (pin "3") (pinfunction "GND_3") (pintype "passive"))
      (node (ref "U7") (pin "4") (pinfunction "GND_4") (pintype "passive"))
      (node (ref "U7") (pin "6") (pinfunction "GND_6") (pintype "passive"))
      (node (ref "U8") (pin "4") (pinfunction "GND_4") (pintype "power_in"))
    )
    (net (code "4") (name "MGMT_TX_UART0_RXD") (class "Default")
      (node (ref "U2") (pin "2") (pinfunction "NO1_2") (pintype "passive"))
    )
    (net (code "5") (name "MGMT_TX_UART0_SEL") (class "Default")
      (node (ref "R17") (pin "2") (pinfunction "2_2") (pintype "passive"))
    )
    (net (code "6") (name "MGMT_TX_UART0_TXD") (class "Default")
      (node (ref "U2") (pin "4") (pinfunction "NO2_4") (pintype "passive"))
    )
    (net (code "7") (name "NRC_TX_XIP_CLK") (class "Default")
      (node (ref "R29") (pin "1") (pinfunction "1_1") (pintype "passive"))
      (node (ref "U1") (pin "30") (pinfunction "XIP_CLK_/_GP00_30") (pintype "passive"))
    )
    (net (code "8") (name "NRC_TX_XIP_CS_N") (class "Default")
      (node (ref "R24") (pin "1") (pinfunction "1_1") (pintype "passive"))
      (node (ref "R27") (pin "1") (pinfunction "1_1") (pintype "passive"))
      (node (ref "U1") (pin "25") (pinfunction "XIP_CS_N_/_GP05_25") (pintype "passive"))
    )
    (net (code "9") (name "NRC_TX_XIP_HOLD_N") (class "Default")
      (node (ref "R23") (pin "1") (pinfunction "1_1") (pintype "passive"))
      (node (ref "R25") (pin "2") (pinfunction "2_2") (pintype "passive"))
      (node (ref "U1") (pin "26") (pinfunction "XIP_HOLD_N_/_GP04_26") (pintype "passive"))
    )
    (net (code "10") (name "NRC_TX_XIP_MISO") (class "Default")
      (node (ref "R28") (pin "2") (pinfunction "2_2") (pintype "passive"))
      (node (ref "U1") (pin "28") (pinfunction "XIP_MISO_/_GP02_28") (pintype "passive"))
    )
    (net (code "11") (name "NRC_TX_XIP_MOSI") (class "Default")
      (node (ref "R30") (pin "2") (pinfunction "2_2") (pintype "passive"))
      (node (ref "U1") (pin "29") (pinfunction "XIP_MOSI_/_GP01_29") (pintype "passive"))
    )
    (net (code "12") (name "NRC_TX_XIP_WP_N") (class "Default")
      (node (ref "R22") (pin "1") (pinfunction "1_1") (pintype "passive"))
      (node (ref "R26") (pin "2") (pinfunction "2_2") (pintype "passive"))
      (node (ref "U1") (pin "27") (pinfunction "XIP_WP_N_/_GP03_27") (pintype "passive"))
    )
    (net (code "13") (name "Net-(C1-Pad1)") (class "Default")
      (node (ref "C1") (pin "1") (pinfunction "1_1") (pintype "passive"))
      (node (ref "R1") (pin "2") (pinfunction "2_2") (pintype "passive"))
    )
    (net (code "14") (name "Net-(C27-Pad2)") (class "Default")
      (node (ref "C27") (pin "2") (pinfunction "2_2") (pintype "passive"))
      (node (ref "C30") (pin "2") (pinfunction "2_2") (pintype "passive"))
      (node (ref "L4") (pin "1") (pinfunction "1_1") (pintype "passive"))
    )
    (net (code "15") (name "Net-(C28-Pad1)") (class "Default")
      (node (ref "C28") (pin "1") (pinfunction "1_1") (pintype "passive"))
      (node (ref "L4") (pin "2") (pinfunction "2_2") (pintype "passive"))
    )
    (net (code "16") (name "Net-(C29-Pad2)") (class "Default")
      (node (ref "C29") (pin "2") (pinfunction "2_2") (pintype "passive"))
      (node (ref "L7") (pin "1") (pinfunction "1_1") (pintype "passive"))
    )
    (net (code "17") (name "Net-(C32-Pad1)") (class "Default")
      (node (ref "C32") (pin "1") (pinfunction "1_1") (pintype "passive"))
      (node (ref "L7") (pin "2") (pinfunction "2_2") (pintype "passive"))
      (node (ref "L8") (pin "1") (pinfunction "1_1") (pintype "passive"))
    )
    (net (code "18") (name "Net-(D2-A)") (class "Default")
      (node (ref "D2") (pin "2") (pinfunction "A_2") (pintype "passive"))
      (node (ref "R3") (pin "2") (pinfunction "2_2") (pintype "passive"))
    )
    (net (code "19") (name "Net-(D3-A)") (class "Default")
      (node (ref "D3") (pin "2") (pinfunction "A_2") (pintype "passive"))
      (node (ref "R14") (pin "2") (pinfunction "2_2") (pintype "passive"))
    )
    (net (code "20") (name "Net-(D3-C)") (class "Default")
      (node (ref "D3") (pin "1") (pinfunction "C_1") (pintype "passive"))
      (node (ref "Q2") (pin "3") (pinfunction "D_3") (pintype "passive"))
    )
    (net (code "21") (name "Net-(D4-A)") (class "Default")
      (node (ref "D4") (pin "2") (pinfunction "A_2") (pintype "passive"))
      (node (ref "R18") (pin "2") (pinfunction "2_2") (pintype "passive"))
    )
    (net (code "22") (name "Net-(D4-C)") (class "Default")
      (node (ref "D4") (pin "1") (pinfunction "C_1") (pintype "passive"))
      (node (ref "Q3") (pin "3") (pinfunction "D_3") (pintype "passive"))
    )
    (net (code "23") (name "Net-(U1-32K_XI)") (class "Default")
      (node (ref "C11") (pin "1") (pinfunction "1_1") (pintype "passive"))
      (node (ref "U1") (pin "31") (pinfunction "32K_XI_31") (pintype "passive"))
      (node (ref "Y1") (pin "1") (pinfunction "1_1") (pintype "passive"))
    )
    (net (code "24") (name "Net-(U1-32K_XO)") (class "Default")
      (node (ref "C9") (pin "1") (pinfunction "1_1") (pintype "passive"))
      (node (ref "U1") (pin "32") (pinfunction "32K_XO_32") (pintype "passive"))
      (node (ref "Y1") (pin "2") (pinfunction "2_2") (pintype "passive"))
    )
    (net (code "25") (name "Net-(U1-PMS_18VO_LDO)") (class "Default")
      (node (ref "C7") (pin "2") (pinfunction "2_2") (pintype "passive"))
      (node (ref "U1") (pin "35") (pinfunction "PMS_18VO_LDO_35") (pintype "passive"))
    )
    (net (code "26") (name "Net-(U1-PMS_CP)") (class "Default")
      (node (ref "R1") (pin "1") (pinfunction "1_1") (pintype "passive"))
      (node (ref "U1") (pin "39") (pinfunction "PMS_CP_39") (pintype "passive"))
    )
    (net (code "27") (name "Net-(U1-PMS_LX)") (class "Default")
      (node (ref "L1") (pin "1") (pinfunction "1_1") (pintype "passive"))
      (node (ref "U1") (pin "37") (pinfunction "PMS_LX_37") (pintype "passive"))
    )
    (net (code "28") (name "Net-(U1-PMS_VO)") (class "Default")
      (node (ref "C3") (pin "2") (pinfunction "2_2") (pintype "passive"))
      (node (ref "L1") (pin "2") (pinfunction "2_2") (pintype "passive"))
      (node (ref "R2") (pin "1") (pinfunction "1_1") (pintype "passive"))
      (node (ref "U1") (pin "38") (pinfunction "PMS_VO_38") (pintype "passive"))
    )
    (net (code "29") (name "Net-(U1-RFI)") (class "Default")
      (node (ref "L3") (pin "2") (pinfunction "2_2") (pintype "passive"))
      (node (ref "U1") (pin "12") (pinfunction "RFI_12") (pintype "passive"))
    )
    (net (code "30") (name "Net-(U1-RFO)") (class "Default")
      (node (ref "C15") (pin "1") (pinfunction "1_1") (pintype "passive"))
      (node (ref "L2") (pin "2") (pinfunction "2_2") (pintype "passive"))
      (node (ref "U1") (pin "11") (pinfunction "RFO_11") (pintype "passive"))
    )
    (net (code "31") (name "Net-(U1-RF_12VO_LDO)") (class "Default")
      (node (ref "C24") (pin "2") (pinfunction "2_2") (pintype "passive"))
      (node (ref "U1") (pin "17") (pinfunction "RF_12VO_LDO_17") (pintype "passive"))
    )
    (net (code "32") (name "Net-(U3-3V3OUT)") (class "Default")
      (node (ref "C22") (pin "2") (pinfunction "2_2") (pintype "passive"))
      (node (ref "C23") (pin "2") (pinfunction "2_2") (pintype "passive"))
      (node (ref "U3") (pin "3") (pinfunction "3V3OUT_3") (pintype "power_in"))
      (node (ref "U3") (pin "9") (pinfunction "VCCIO_9") (pintype "power_in"))
    )
    (net (code "33") (name "Net-(U3-RXD)") (class "Default")
      (node (ref "R7") (pin "1") (pinfunction "1_1") (pintype "passive"))
      (node (ref "U3") (pin "10") (pinfunction "RXD_10") (pintype "output"))
    )
    (net (code "34") (name "Net-(U3-TXD)") (class "Default")
      (node (ref "R6") (pin "1") (pinfunction "1_1") (pintype "passive"))
      (node (ref "U3") (pin "7") (pinfunction "TXD_7") (pintype "output"))
    )
    (net (code "35") (name "Net-(U3-~{RESET})") (class "Default")
      (node (ref "C21") (pin "1") (pinfunction "1_1") (pintype "passive"))
      (node (ref "R8") (pin "2") (pinfunction "2_2") (pintype "passive"))
      (node (ref "R9") (pin "2") (pinfunction "2_2") (pintype "passive"))
      (node (ref "U3") (pin "2") (pinfunction "~{RESET}_2") (pintype "input"))
    )
    (net (code "36") (name "Net-(U5-OUT1)") (class "Default")
      (node (ref "C28") (pin "2") (pinfunction "2_2") (pintype "passive"))
      (node (ref "U5") (pin "1") (pinfunction "OUT1_1") (pintype "output"))
    )
    (net (code "37") (name "Net-(U5-OUT2)") (class "Default")
      (node (ref "C26") (pin "2") (pinfunction "2_2") (pintype "passive"))
      (node (ref "U5") (pin "3") (pinfunction "OUT2_3") (pintype "output"))
    )
    (net (code "38") (name "Net-(U5-RFC)") (class "Default")
      (node (ref "C29") (pin "1") (pinfunction "1_1") (pintype "passive"))
      (node (ref "U5") (pin "5") (pinfunction "RFC_5") (pintype "passive"))
    )
    (net (code "39") (name "Net-(U7-OUTPUT)") (class "Default")
      (node (ref "C27") (pin "1") (pinfunction "1_1") (pintype "passive"))
      (node (ref "U7") (pin "5") (pinfunction "OUTPUT_5") (pintype "passive"))
    )
    (net (code "40") (name "Net-(U8-CS#)") (class "Default")
      (node (ref "R27") (pin "2") (pinfunction "2_2") (pintype "passive"))
      (node (ref "U8") (pin "1") (pinfunction "CS#_1") (pintype "input"))
    )
    (net (code "41") (name "Net-(U8-HOLD#{slash}SIO3)") (class "Default")
      (node (ref "R25") (pin "1") (pinfunction "1_1") (pintype "passive"))
      (node (ref "U8") (pin "7") (pinfunction "HOLD#/SIO3_7") (pintype "bidirectional"))
    )
    (net (code "42") (name "Net-(U8-SCLK)") (class "Default")
      (node (ref "R29") (pin "2") (pinfunction "2_2") (pintype "passive"))
      (node (ref "U8") (pin "6") (pinfunction "SCLK_6") (pintype "input"))
    )
    (net (code "43") (name "Net-(U8-SI{slash}SIO0)") (class "Default")
      (node (ref "R30") (pin "1") (pinfunction "1_1") (pintype "passive"))
      (node (ref "U8") (pin "5") (pinfunction "SI/SIO0_5") (pintype "bidirectional"))
    )
    (net (code "44") (name "Net-(U8-SO{slash}SIO1)") (class "Default")
      (node (ref "R28") (pin "1") (pinfunction "1_1") (pintype "passive"))
      (node (ref "U8") (pin "2") (pinfunction "SO/SIO1_2") (pintype "bidirectional"))
    )
    (net (code "45") (name "Net-(U8-WP#{slash}SIO2)") (class "Default")
      (node (ref "R26") (pin "1") (pinfunction "1_1") (pintype "passive"))
      (node (ref "U8") (pin "3") (pinfunction "WP#/SIO2_3") (pintype "bidirectional"))
    )
    (net (code "46") (name "P1V1_TX") (class "Default")
      (node (ref "C6") (pin "2") (pinfunction "2_2") (pintype "passive"))
      (node (ref "C8") (pin "2") (pinfunction "2_2") (pintype "passive"))
      (node (ref "U1") (pin "1") (pinfunction "VDDC_1") (pintype "passive"))
      (node (ref "U1") (pin "33") (pinfunction "VDDC_33") (pintype "passive"))
      (node (ref "U1") (pin "34") (pinfunction "PMS_VO_LDO_34") (pintype "passive"))
    )
    (net (code "47") (name "P1V45_TX") (class "Default")
      (node (ref "C2") (pin "1") (pinfunction "1_1") (pintype "passive"))
      (node (ref "C20") (pin "2") (pinfunction "2_2") (pintype "passive"))
      (node (ref "R2") (pin "2") (pinfunction "2_2") (pintype "passive"))
      (node (ref "U1") (pin "14") (pinfunction "RF_14VI_14") (pintype "passive"))
    )
    (net (code "48") (name "SW_TX_RST") (class "Default")
      (node (ref "Q1") (pin "1") (pinfunction "G_1") (pintype "passive"))
      (node (ref "R13") (pin "2") (pinfunction "2_2") (pintype "passive"))
    )
    (net (code "49") (name "TX_32MHz") (class "Default")
      (node (ref "U1") (pin "15") (pinfunction "XTAL_IN_15") (pintype "passive"))
    )
    (net (code "50") (name "TX_FTDI_RXD") (class "Default")
      (node (ref "R7") (pin "2") (pinfunction "2_2") (pintype "passive"))
      (node (ref "U2") (pin "10") (pinfunction "NC1_10") (pintype "passive"))
    )
    (net (code "51") (name "TX_FTDI_TXD") (class "Default")
      (node (ref "R6") (pin "2") (pinfunction "2_2") (pintype "passive"))
      (node (ref "U2") (pin "8") (pinfunction "NC2_8") (pintype "passive"))
    )
    (net (code "52") (name "TX_GP15") (class "Default")
      (node (ref "U1") (pin "20") (pinfunction "GP15_/_RX_SEL_/_RF_TEST2_20") (pintype "passive"))
      (node (ref "U4") (pin "2") (pinfunction "A_2") (pintype "input"))
      (node (ref "U5") (pin "6") (pinfunction "VCTL1_6") (pintype "power_in"))
    )
    (net (code "53") (name "TX_GP15_INV") (class "Default")
      (node (ref "U4") (pin "4") (pinfunction "Y_4") (pintype "output"))
      (node (ref "U5") (pin "4") (pinfunction "VCTL2_4") (pintype "power_in"))
    )
    (net (code "54") (name "TX_GP16") (class "Default")
      (node (ref "U1") (pin "21") (pinfunction "GP16_/_PWR_DN_/_RF_TEST3_21") (pintype "passive"))
    )
    (net (code "55") (name "TX_GP17") (class "Default")
      (node (ref "U1") (pin "18") (pinfunction "GP17_/_ADCIN0_/_RF_TEST0_18") (pintype "passive"))
    )
    (net (code "56") (name "TX_GP18") (class "Default")
      (node (ref "U1") (pin "19") (pinfunction "GP18_/_ADCIN1_/_RF_TEST1_19") (pintype "passive"))
    )
    (net (code "57") (name "TX_GP20") (class "Default")
      (node (ref "P1") (pin "5") (pinfunction "5_5") (pintype "passive"))
      (node (ref "U1") (pin "7") (pinfunction "GP20_7") (pintype "passive"))
    )
    (net (code "58") (name "TX_GP24") (class "Default")
      (node (ref "U1") (pin "22") (pinfunction "GP24_/_PA_EN_22") (pintype "passive"))
    )
    (net (code "59") (name "TX_GP25") (class "Default")
      (node (ref "D2") (pin "1") (pinfunction "C_1") (pintype "passive"))
      (node (ref "U1") (pin "23") (pinfunction "GP25_23") (pintype "passive"))
    )
    (net (code "60") (name "TX_HSPI_CS_N") (class "Default")
      (node (ref "R4") (pin "1") (pinfunction "1_1") (pintype "passive"))
      (node (ref "U1") (pin "41") (pinfunction "HSPI_CS_N_/_GP28_41") (pintype "passive"))
    )
    (net (code "61") (name "TX_HSPI_EIRQ_N") (class "Default")
      (node (ref "R5") (pin "1") (pinfunction "1_1") (pintype "passive"))
      (node (ref "U1") (pin "47") (pinfunction "HSPI_EIRQ_N_/_GP30_47") (pintype "passive"))
    )
    (net (code "62") (name "TX_HSPI_MISO") (class "Default")
      (node (ref "U1") (pin "42") (pinfunction "HSPI_MISO_/_GP29_42") (pintype "passive"))
    )
    (net (code "63") (name "TX_HSPI_MOSI") (class "Default")
      (node (ref "U1") (pin "43") (pinfunction "HSPI_MOSI_/_GP06_43") (pintype "passive"))
    )
    (net (code "64") (name "TX_HSPI_SCLK") (class "Default")
      (node (ref "U1") (pin "44") (pinfunction "HSPI_CLK_/_GP07_44") (pintype "passive"))
    )
    (net (code "65") (name "TX_MODE") (class "Default")
      (node (ref "Q3") (pin "1") (pinfunction "G_1") (pintype "passive"))
      (node (ref "R20") (pin "1") (pinfunction "1_1") (pintype "passive"))
      (node (ref "SW3") (pin "2") (pinfunction "2_2") (pintype "passive"))
      (node (ref "U1") (pin "8") (pinfunction "MODE_/_GP19_8") (pintype "passive"))
    )
    (net (code "66") (name "TX_PMS_RST_N") (class "Default")
      (node (ref "C49") (pin "1") (pinfunction "1_1") (pintype "passive"))
      (node (ref "P1") (pin "2") (pinfunction "2_2") (pintype "passive"))
      (node (ref "Q1") (pin "3") (pinfunction "D_3") (pintype "passive"))
      (node (ref "R19") (pin "1") (pinfunction "1_1") (pintype "passive"))
      (node (ref "R21") (pin "2") (pinfunction "2_2") (pintype "passive"))
      (node (ref "SW2") (pin "1") (pinfunction "1_1") (pintype "passive"))
      (node (ref "SW2") (pin "2") (pinfunction "2_2") (pintype "passive"))
      (node (ref "U1") (pin "40") (pinfunction "RST_N_/_PMS_POR_N_40") (pintype "passive"))
    )
    (net (code "67") (name "TX_RFIO") (class "Default")
      (node (ref "C31") (pin "2") (pinfunction "2_2") (pintype "passive"))
      (node (ref "L8") (pin "2") (pinfunction "2_2") (pintype "passive"))
    )
    (net (code "68") (name "TX_RF_INPUT") (class "Default")
      (node (ref "C18") (pin "1") (pinfunction "1_1") (pintype "passive"))
      (node (ref "L3") (pin "1") (pinfunction "1_1") (pintype "passive"))
      (node (ref "U7") (pin "2") (pinfunction "INPUT_2") (pintype "passive"))
    )
    (net (code "69") (name "TX_RF_OUTPUT") (class "Default")
      (node (ref "C14") (pin "1") (pinfunction "1_1") (pintype "passive"))
      (node (ref "C26") (pin "1") (pinfunction "1_1") (pintype "passive"))
      (node (ref "L2") (pin "1") (pinfunction "1_1") (pintype "passive"))
    )
    (net (code "70") (name "TX_SWDCK") (class "Default")
      (node (ref "P1") (pin "6") (pinfunction "6_6") (pintype "passive"))
      (node (ref "R11") (pin "1") (pinfunction "1_1") (pintype "passive"))
      (node (ref "U1") (pin "2") (pinfunction "TCK_/_SWDCK_/_GP11_2") (pintype "passive"))
    )
    (net (code "71") (name "TX_SWDIO") (class "Default")
      (node (ref "P1") (pin "4") (pinfunction "4_4") (pintype "passive"))
      (node (ref "R12") (pin "1") (pinfunction "1_1") (pintype "passive"))
      (node (ref "U1") (pin "48") (pinfunction "TMS_/_SWDIO_/_GP10_48") (pintype "passive"))
    )
    (net (code "72") (name "TX_TDI") (class "Default")
      (node (ref "P1") (pin "10") (pinfunction "10_10") (pintype "passive"))
      (node (ref "U1") (pin "4") (pinfunction "TDI_/_GP13_4") (pintype "passive"))
    )
    (net (code "73") (name "TX_TDO") (class "Default")
      (node (ref "P1") (pin "8") (pinfunction "8_8") (pintype "passive"))
      (node (ref "U1") (pin "3") (pinfunction "TDO_/_GP12_3") (pintype "passive"))
    )
    (net (code "74") (name "TX_TRST_N") (class "Default")
      (node (ref "P1") (pin "7") (pinfunction "7_7") (pintype "passive"))
      (node (ref "R10") (pin "1") (pinfunction "1_1") (pintype "passive"))
      (node (ref "R15") (pin "2") (pinfunction "2_2") (pintype "passive"))
      (node (ref "U1") (pin "5") (pinfunction "GP14_/_TRST_N_5") (pintype "passive"))
    )
    (net (code "75") (name "TX_UART0_RXD") (class "Default")
      (node (ref "U1") (pin "46") (pinfunction "UART0_RXD_/_GP09_46") (pintype "passive"))
      (node (ref "U2") (pin "7") (pinfunction "COM2_7") (pintype "passive"))
    )
    (net (code "76") (name "TX_UART0_SEL") (class "Default")
      (node (ref "Q2") (pin "1") (pinfunction "G_1") (pintype "passive"))
      (node (ref "R16") (pin "1") (pinfunction "1_1") (pintype "passive"))
      (node (ref "R17") (pin "1") (pinfunction "1_1") (pintype "passive"))
      (node (ref "SW1") (pin "2") (pinfunction "2_2") (pintype "passive"))
      (node (ref "U2") (pin "1") (pinfunction "SEL1_1") (pintype "input"))
      (node (ref "U2") (pin "5") (pinfunction "SEL2_5") (pintype "input"))
    )
    (net (code "77") (name "TX_UART0_TXD") (class "Default")
      (node (ref "U1") (pin "45") (pinfunction "UART0_TXD_/_GP08_45") (pintype "passive"))
      (node (ref "U2") (pin "11") (pinfunction "COM1_11") (pintype "passive"))
    )
    (net (code "78") (name "TX_USB_D_N") (class "Default")
      (node (ref "U3") (pin "1") (pinfunction "USBDM_1") (pintype "bidirectional"))
    )
    (net (code "79") (name "TX_USB_D_P") (class "Default")
      (node (ref "U3") (pin "12") (pinfunction "USBDP_12") (pintype "bidirectional"))
    )
    (net (code "80") (name "unconnected-(U1-XTAL_OUT-Pad16)") (class "Default")
      (node (ref "U1") (pin "16") (pinfunction "XTAL_OUT_16") (pintype "passive"))
    )
    (net (code "81") (name "unconnected-(U3-CBUS0-Pad6)") (class "Default")
      (node (ref "U3") (pin "6") (pinfunction "CBUS0_6") (pintype "bidirectional"))
    )
    (net (code "82") (name "unconnected-(U3-~{CTS}-Pad11)") (class "Default")
      (node (ref "U3") (pin "11") (pinfunction "~{CTS}_11") (pintype "input"))
    )
    (net (code "83") (name "unconnected-(U3-~{RTS}-Pad8)") (class "Default")
      (node (ref "U3") (pin "8") (pinfunction "~{RTS}_8") (pintype "input"))
    )
    (net (code "84") (name "unconnected-(U4B-NC-Pad1)") (class "Default")
      (node (ref "U4") (pin "1") (pinfunction "NC_1") (pintype "passive"))
    )
  )
)
